# 05-Front_Panel_SFP_1.net
KiCad netlist of a schematic drawn in Altium Designer
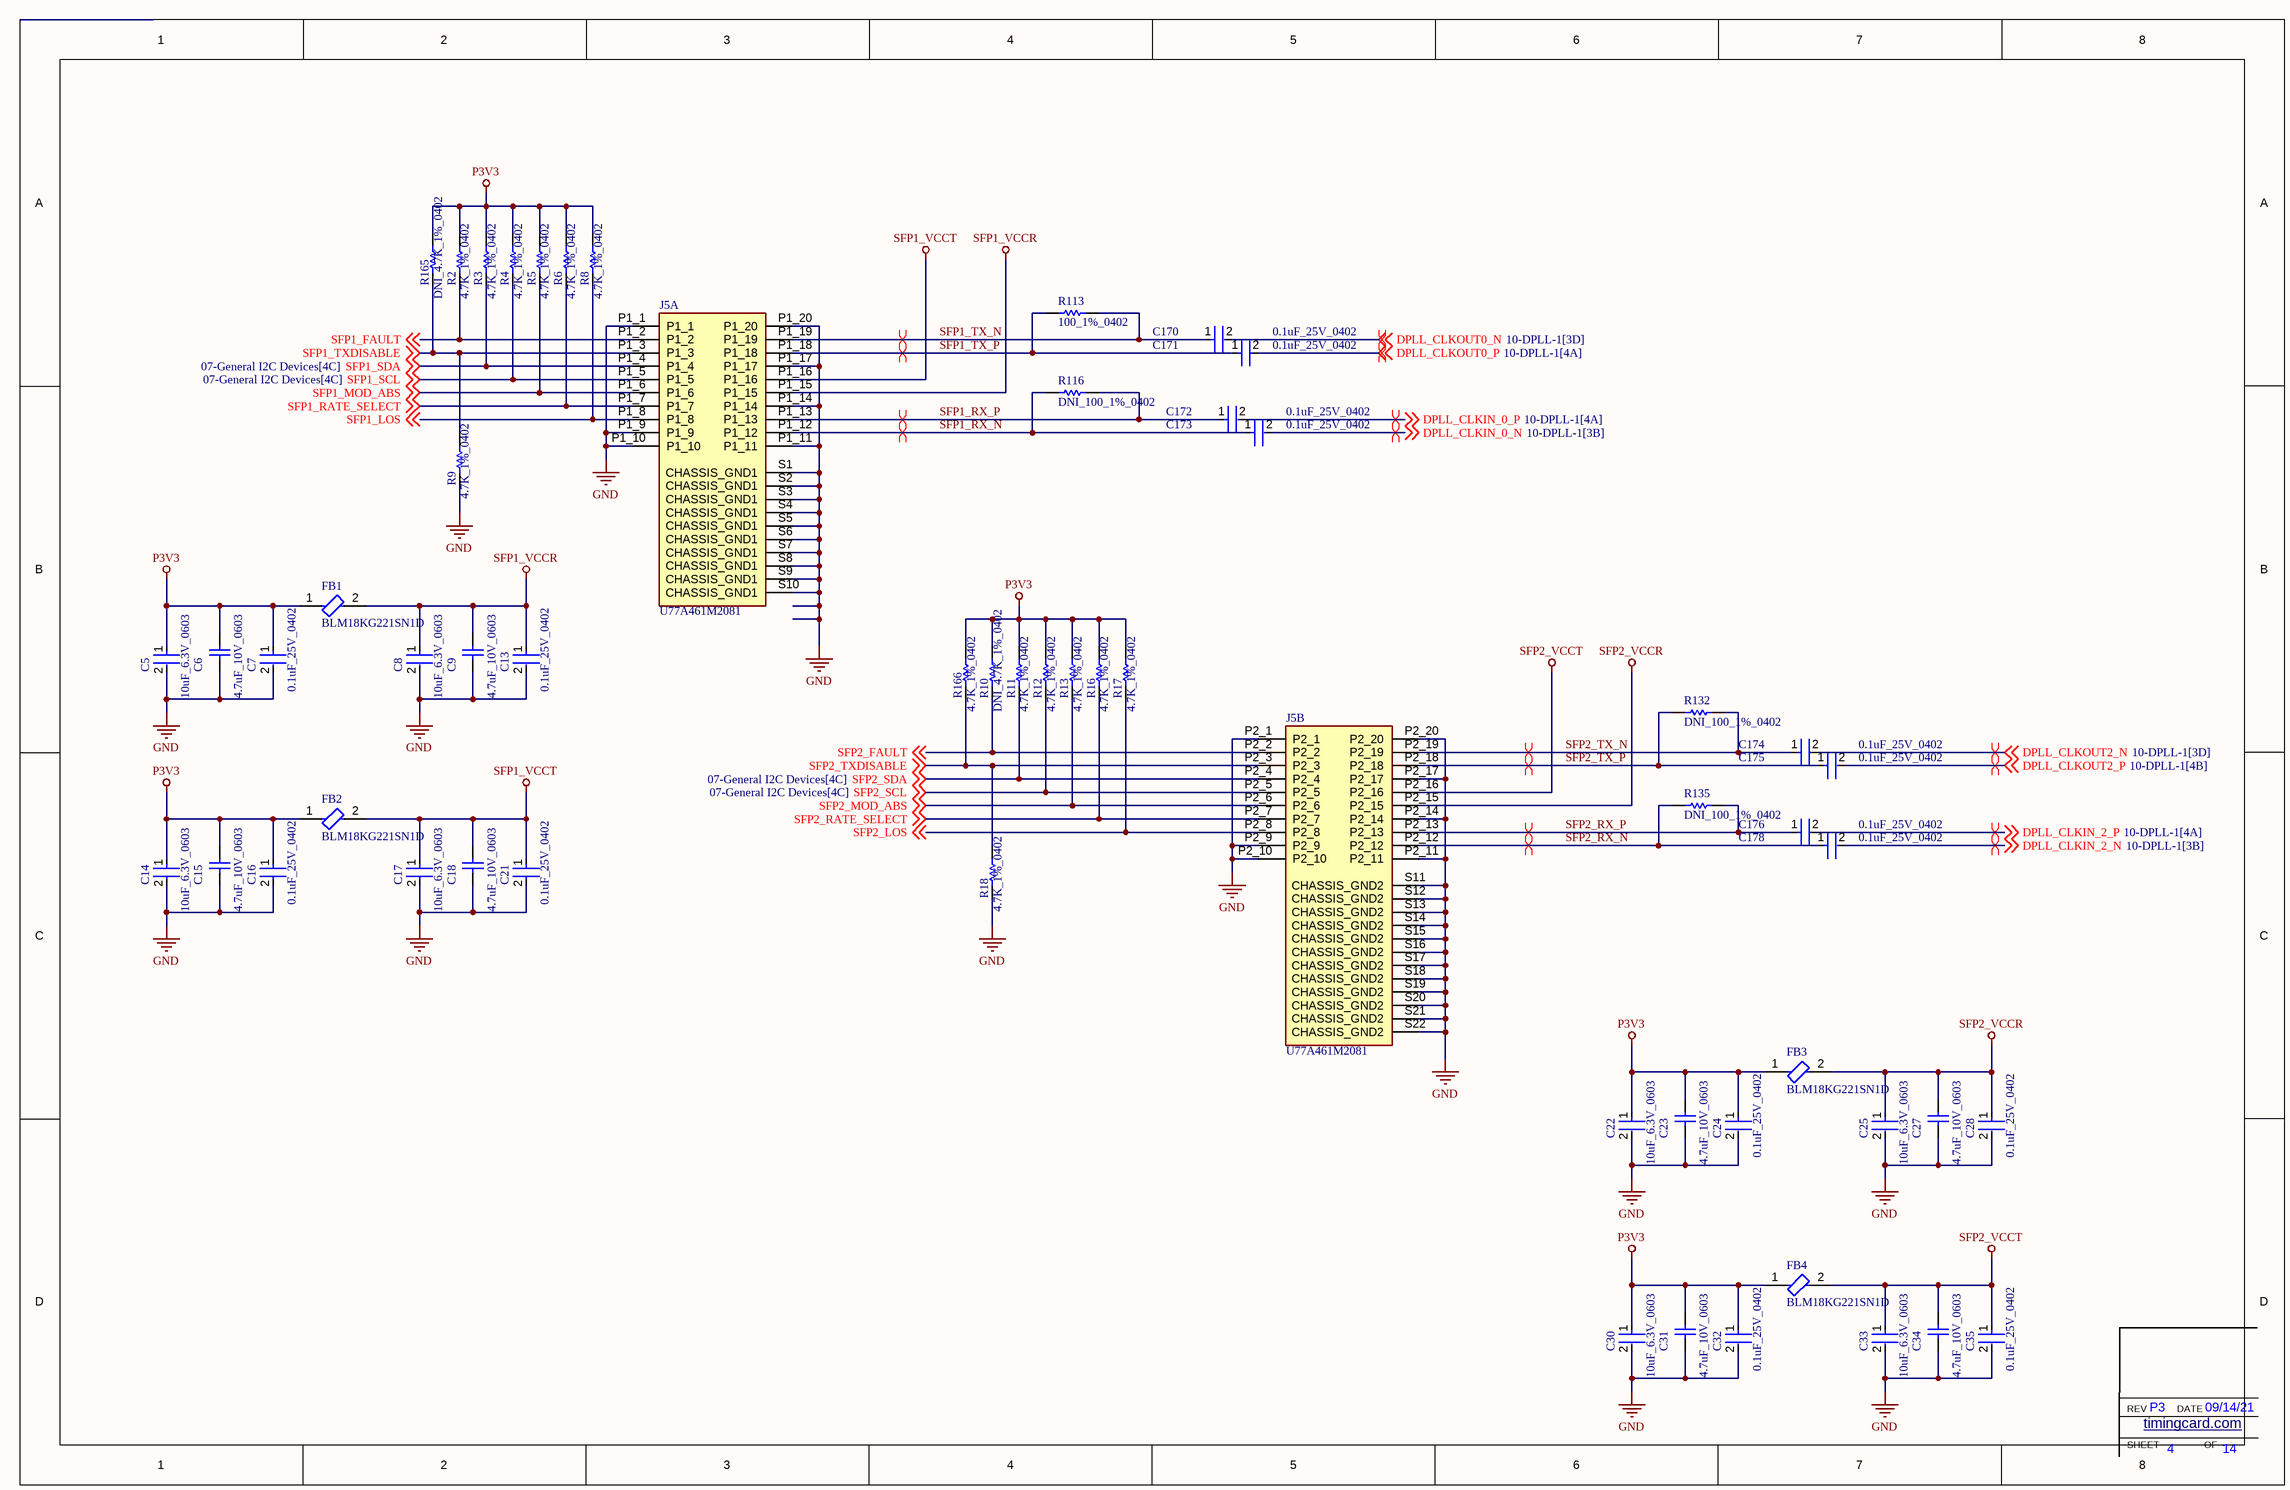
[diagram p0: 05-Front Panel SFP_1.SchDoc]

(export (version "E")
  (design (tool "Eeschema 10.0.6"))
  (components
    (comp (ref "C5")
      (value "10uF_6.3V_0603")
      (footprint "FP-C0603C106M9PACTU-MFG")
      (description "CAP CER 10UF 6.3V X5R 0603")
      (fields
        (field (name "MANUFACTURER PART NUMBER") "C0603C106M9PACTU")
        (field (name "MANUFACTURER") "Kemet")
      )
      (libsource (lib "Altium Content Vault") (part "b4654b650e69147ec39a6b967a45e02"))
    )
    (comp (ref "C6")
      (value "4.7uF_10V_0603")
      (footprint "CAPC1608X87X35NL15T15")
      (fields (field (name "PART NUMBER") "C0603C475K8PACTU") (field (name "MANUFACTURER") "Kemet"))
      (libsource (lib "Altium Content Vault") (part "CAP"))
    )
    (comp (ref "C7")
      (value "0.1uF_25V_0402")
      (footprint "FP-0402-L_1_0_1-W_0_5_0_1-IPC_C")
      (description "General Purpose Ceramic Capacitor, 0402, 100nF, 10%, X7R, 15%, 25V")
      (fields (field (name "VOLTAGE") "25V") (field (name "TOLERANCE") "10%"))
      (libsource (lib "Altium Content Vault") (part "b4654b650e69147ec39a6b967a45e02"))
    )
    (comp (ref "C8")
      (value "10uF_6.3V_0603")
      (footprint "FP-C0603C106M9PACTU-MFG")
      (description "CAP CER 10UF 6.3V X5R 0603")
      (fields
        (field (name "MANUFACTURER PART NUMBER") "C0603C106M9PACTU")
        (field (name "MANUFACTURER") "Kemet")
      )
      (libsource (lib "Altium Content Vault") (part "b4654b650e69147ec39a6b967a45e02"))
    )
    (comp (ref "C9")
      (value "4.7uF_10V_0603")
      (footprint "CAPC1608X87X35NL15T15")
      (fields (field (name "PART NUMBER") "C0603C475K8PACTU") (field (name "MANUFACTURER") "Kemet"))
      (libsource (lib "Altium Content Vault") (part "CAP"))
    )
    (comp (ref "C13")
      (value "0.1uF_25V_0402")
      (footprint "FP-0402-L_1_0_1-W_0_5_0_1-IPC_C")
      (description "General Purpose Ceramic Capacitor, 0402, 100nF, 10%, X7R, 15%, 25V")
      (fields (field (name "VOLTAGE") "25V") (field (name "TOLERANCE") "10%"))
      (libsource (lib "Altium Content Vault") (part "b4654b650e69147ec39a6b967a45e02"))
    )
    (comp (ref "C14")
      (value "10uF_6.3V_0603")
      (footprint "FP-C0603C106M9PACTU-MFG")
      (description "CAP CER 10UF 6.3V X5R 0603")
      (fields
        (field (name "MANUFACTURER PART NUMBER") "C0603C106M9PACTU")
        (field (name "MANUFACTURER") "Kemet")
      )
      (libsource (lib "Altium Content Vault") (part "b4654b650e69147ec39a6b967a45e02"))
    )
    (comp (ref "C15")
      (value "4.7uF_10V_0603")
      (footprint "CAPC1608X87X35NL15T15")
      (fields (field (name "PART NUMBER") "C0603C475K8PACTU") (field (name "MANUFACTURER") "Kemet"))
      (libsource (lib "Altium Content Vault") (part "CAP"))
    )
    (comp (ref "C16")
      (value "0.1uF_25V_0402")
      (footprint "FP-0402-L_1_0_1-W_0_5_0_1-IPC_C")
      (description "General Purpose Ceramic Capacitor, 0402, 100nF, 10%, X7R, 15%, 25V")
      (fields (field (name "VOLTAGE") "25V") (field (name "TOLERANCE") "10%"))
      (libsource (lib "Altium Content Vault") (part "b4654b650e69147ec39a6b967a45e02"))
    )
    (comp (ref "C17")
      (value "10uF_6.3V_0603")
      (footprint "FP-C0603C106M9PACTU-MFG")
      (description "CAP CER 10UF 6.3V X5R 0603")
      (fields
        (field (name "MANUFACTURER PART NUMBER") "C0603C106M9PACTU")
        (field (name "MANUFACTURER") "Kemet")
      )
      (libsource (lib "Altium Content Vault") (part "b4654b650e69147ec39a6b967a45e02"))
    )
    (comp (ref "C18")
      (value "4.7uF_10V_0603")
      (footprint "CAPC1608X87X35NL15T15")
      (fields (field (name "PART NUMBER") "C0603C475K8PACTU") (field (name "MANUFACTURER") "Kemet"))
      (libsource (lib "Altium Content Vault") (part "CAP"))
    )
    (comp (ref "C21")
      (value "0.1uF_25V_0402")
      (footprint "FP-0402-L_1_0_1-W_0_5_0_1-IPC_C")
      (description "General Purpose Ceramic Capacitor, 0402, 100nF, 10%, X7R, 15%, 25V")
      (fields (field (name "VOLTAGE") "25V") (field (name "TOLERANCE") "10%"))
      (libsource (lib "Altium Content Vault") (part "b4654b650e69147ec39a6b967a45e02"))
    )
    (comp (ref "C22")
      (value "10uF_6.3V_0603")
      (footprint "FP-C0603C106M9PACTU-MFG")
      (description "CAP CER 10UF 6.3V X5R 0603")
      (fields
        (field (name "MANUFACTURER PART NUMBER") "C0603C106M9PACTU")
        (field (name "MANUFACTURER") "Kemet")
      )
      (libsource (lib "Altium Content Vault") (part "b4654b650e69147ec39a6b967a45e02"))
    )
    (comp (ref "C23")
      (value "4.7uF_10V_0603")
      (footprint "CAPC1608X87X35NL15T15")
      (fields (field (name "PART NUMBER") "C0603C475K8PACTU") (field (name "MANUFACTURER") "Kemet"))
      (libsource (lib "Altium Content Vault") (part "CAP"))
    )
    (comp (ref "C24")
      (value "0.1uF_25V_0402")
      (footprint "FP-0402-L_1_0_1-W_0_5_0_1-IPC_C")
      (description "General Purpose Ceramic Capacitor, 0402, 100nF, 10%, X7R, 15%, 25V")
      (fields (field (name "VOLTAGE") "25V") (field (name "TOLERANCE") "10%"))
      (libsource (lib "Altium Content Vault") (part "b4654b650e69147ec39a6b967a45e02"))
    )
    (comp (ref "C25")
      (value "10uF_6.3V_0603")
      (footprint "FP-C0603C106M9PACTU-MFG")
      (description "CAP CER 10UF 6.3V X5R 0603")
      (fields
        (field (name "MANUFACTURER PART NUMBER") "C0603C106M9PACTU")
        (field (name "MANUFACTURER") "Kemet")
      )
      (libsource (lib "Altium Content Vault") (part "b4654b650e69147ec39a6b967a45e02"))
    )
    (comp (ref "C27")
      (value "4.7uF_10V_0603")
      (footprint "CAPC1608X87X35NL15T15")
      (fields (field (name "PART NUMBER") "C0603C475K8PACTU") (field (name "MANUFACTURER") "Kemet"))
      (libsource (lib "Altium Content Vault") (part "CAP"))
    )
    (comp (ref "C28")
      (value "0.1uF_25V_0402")
      (footprint "FP-0402-L_1_0_1-W_0_5_0_1-IPC_C")
      (description "General Purpose Ceramic Capacitor, 0402, 100nF, 10%, X7R, 15%, 25V")
      (fields (field (name "VOLTAGE") "25V") (field (name "TOLERANCE") "10%"))
      (libsource (lib "Altium Content Vault") (part "b4654b650e69147ec39a6b967a45e02"))
    )
    (comp (ref "C30")
      (value "10uF_6.3V_0603")
      (footprint "FP-C0603C106M9PACTU-MFG")
      (description "CAP CER 10UF 6.3V X5R 0603")
      (fields
        (field (name "MANUFACTURER PART NUMBER") "C0603C106M9PACTU")
        (field (name "MANUFACTURER") "Kemet")
      )
      (libsource (lib "Altium Content Vault") (part "b4654b650e69147ec39a6b967a45e02"))
    )
    (comp (ref "C31")
      (value "4.7uF_10V_0603")
      (footprint "CAPC1608X87X35NL15T15")
      (fields (field (name "PART NUMBER") "C0603C475K8PACTU") (field (name "MANUFACTURER") "Kemet"))
      (libsource (lib "Altium Content Vault") (part "CAP"))
    )
    (comp (ref "C32")
      (value "0.1uF_25V_0402")
      (footprint "FP-0402-L_1_0_1-W_0_5_0_1-IPC_C")
      (description "General Purpose Ceramic Capacitor, 0402, 100nF, 10%, X7R, 15%, 25V")
      (fields (field (name "VOLTAGE") "25V") (field (name "TOLERANCE") "10%"))
      (libsource (lib "Altium Content Vault") (part "b4654b650e69147ec39a6b967a45e02"))
    )
    (comp (ref "C33")
      (value "10uF_6.3V_0603")
      (footprint "FP-C0603C106M9PACTU-MFG")
      (description "CAP CER 10UF 6.3V X5R 0603")
      (fields
        (field (name "MANUFACTURER PART NUMBER") "C0603C106M9PACTU")
        (field (name "MANUFACTURER") "Kemet")
      )
      (libsource (lib "Altium Content Vault") (part "b4654b650e69147ec39a6b967a45e02"))
    )
    (comp (ref "C34")
      (value "4.7uF_10V_0603")
      (footprint "CAPC1608X87X35NL15T15")
      (fields (field (name "PART NUMBER") "C0603C475K8PACTU") (field (name "MANUFACTURER") "Kemet"))
      (libsource (lib "Altium Content Vault") (part "CAP"))
    )
    (comp (ref "C35")
      (value "0.1uF_25V_0402")
      (footprint "FP-0402-L_1_0_1-W_0_5_0_1-IPC_C")
      (description "General Purpose Ceramic Capacitor, 0402, 100nF, 10%, X7R, 15%, 25V")
      (fields (field (name "VOLTAGE") "25V") (field (name "TOLERANCE") "10%"))
      (libsource (lib "Altium Content Vault") (part "b4654b650e69147ec39a6b967a45e02"))
    )
    (comp (ref "C170")
      (value "0.1uF_25V_0402")
      (footprint "FP-0402-L_1_0_1-W_0_5_0_1-IPC_C")
      (description "General Purpose Ceramic Capacitor, 0402, 100nF, 10%, X7R, 15%, 25V")
      (fields (field (name "VOLTAGE") "25V") (field (name "TOLERANCE") "10%"))
      (libsource (lib "Altium Content Vault") (part "b4654b650e69147ec39a6b967a45e02"))
    )
    (comp (ref "C171")
      (value "0.1uF_25V_0402")
      (footprint "FP-0402-L_1_0_1-W_0_5_0_1-IPC_C")
      (description "General Purpose Ceramic Capacitor, 0402, 100nF, 10%, X7R, 15%, 25V")
      (fields (field (name "VOLTAGE") "25V") (field (name "TOLERANCE") "10%"))
      (libsource (lib "Altium Content Vault") (part "b4654b650e69147ec39a6b967a45e02"))
    )
    (comp (ref "C172")
      (value "0.1uF_25V_0402")
      (footprint "FP-0402-L_1_0_1-W_0_5_0_1-IPC_C")
      (description "General Purpose Ceramic Capacitor, 0402, 100nF, 10%, X7R, 15%, 25V")
      (fields (field (name "VOLTAGE") "25V") (field (name "TOLERANCE") "10%"))
      (libsource (lib "Altium Content Vault") (part "b4654b650e69147ec39a6b967a45e02"))
    )
    (comp (ref "C173")
      (value "0.1uF_25V_0402")
      (footprint "FP-0402-L_1_0_1-W_0_5_0_1-IPC_C")
      (description "General Purpose Ceramic Capacitor, 0402, 100nF, 10%, X7R, 15%, 25V")
      (fields (field (name "VOLTAGE") "25V") (field (name "TOLERANCE") "10%"))
      (libsource (lib "Altium Content Vault") (part "b4654b650e69147ec39a6b967a45e02"))
    )
    (comp (ref "C174")
      (value "0.1uF_25V_0402")
      (footprint "FP-0402-L_1_0_1-W_0_5_0_1-IPC_C")
      (description "General Purpose Ceramic Capacitor, 0402, 100nF, 10%, X7R, 15%, 25V")
      (fields (field (name "VOLTAGE") "25V") (field (name "TOLERANCE") "10%"))
      (libsource (lib "Altium Content Vault") (part "b4654b650e69147ec39a6b967a45e02"))
    )
    (comp (ref "C175")
      (value "0.1uF_25V_0402")
      (footprint "FP-0402-L_1_0_1-W_0_5_0_1-IPC_C")
      (description "General Purpose Ceramic Capacitor, 0402, 100nF, 10%, X7R, 15%, 25V")
      (fields (field (name "VOLTAGE") "25V") (field (name "TOLERANCE") "10%"))
      (libsource (lib "Altium Content Vault") (part "b4654b650e69147ec39a6b967a45e02"))
    )
    (comp (ref "C176")
      (value "0.1uF_25V_0402")
      (footprint "FP-0402-L_1_0_1-W_0_5_0_1-IPC_C")
      (description "General Purpose Ceramic Capacitor, 0402, 100nF, 10%, X7R, 15%, 25V")
      (fields (field (name "VOLTAGE") "25V") (field (name "TOLERANCE") "10%"))
      (libsource (lib "Altium Content Vault") (part "b4654b650e69147ec39a6b967a45e02"))
    )
    (comp (ref "C178")
      (value "0.1uF_25V_0402")
      (footprint "FP-0402-L_1_0_1-W_0_5_0_1-IPC_C")
      (description "General Purpose Ceramic Capacitor, 0402, 100nF, 10%, X7R, 15%, 25V")
      (fields (field (name "VOLTAGE") "25V") (field (name "TOLERANCE") "10%"))
      (libsource (lib "Altium Content Vault") (part "b4654b650e69147ec39a6b967a45e02"))
    )
    (comp (ref "FB1")
      (value "BLM18KG221SN1D")
      (footprint "FP-BLM18-0_15-t0_8-IPC_B")
      (description "Chip Ferrite Bead, 0603, 220Ω @ 100MHz, 0.05Ω, 25%, 2.2A")
      (fields (field (name "TOLERANCE") "25%"))
      (libsource (lib "Altium Content Vault") (part "5f30dd21d616792df468990f7003faa"))
    )
    (comp (ref "FB2")
      (value "BLM18KG221SN1D")
      (footprint "FP-BLM18-0_15-t0_8-IPC_B")
      (description "Chip Ferrite Bead, 0603, 220Ω @ 100MHz, 0.05Ω, 25%, 2.2A")
      (fields (field (name "TOLERANCE") "25%"))
      (libsource (lib "Altium Content Vault") (part "5f30dd21d616792df468990f7003faa"))
    )
    (comp (ref "FB3")
      (value "BLM18KG221SN1D")
      (footprint "FP-BLM18-0_15-t0_8-IPC_B")
      (description "Chip Ferrite Bead, 0603, 220Ω @ 100MHz, 0.05Ω, 25%, 2.2A")
      (fields (field (name "TOLERANCE") "25%"))
      (libsource (lib "Altium Content Vault") (part "5f30dd21d616792df468990f7003faa"))
    )
    (comp (ref "FB4")
      (value "BLM18KG221SN1D")
      (footprint "FP-BLM18-0_15-t0_8-IPC_B")
      (description "Chip Ferrite Bead, 0603, 220Ω @ 100MHz, 0.05Ω, 25%, 2.2A")
      (fields (field (name "TOLERANCE") "25%"))
      (libsource (lib "Altium Content Vault") (part "5f30dd21d616792df468990f7003faa"))
    )
    (comp (ref "J5")
      (value "U77A461M2081")
      (footprint "AMPHENOL_U77A461M2081")
      (fields (field (name "MF") "AMPHENOL ICC / FCI"))
      (libsource (lib "U77A461M2081") (part "U77A461M2081"))
    )
    (comp (ref "R2")
      (value "4.7K_1%_0402")
      (footprint "RESC1005X40X25NL10T10")
      (fields (field (name "MANUFACTURER") "Bourns") (field (name "PART NUMBER") "CR0402-FX-4701GLF"))
      (libsource (lib "Altium Content Vault") (part "RES"))
    )
    (comp (ref "R3")
      (value "4.7K_1%_0402")
      (footprint "RESC1005X40X25NL10T10")
      (fields (field (name "MANUFACTURER") "Bourns") (field (name "PART NUMBER") "CR0402-FX-4701GLF"))
      (libsource (lib "Altium Content Vault") (part "RES"))
    )
    (comp (ref "R4")
      (value "4.7K_1%_0402")
      (footprint "RESC1005X40X25NL10T10")
      (fields (field (name "MANUFACTURER") "Bourns") (field (name "PART NUMBER") "CR0402-FX-4701GLF"))
      (libsource (lib "Altium Content Vault") (part "RES"))
    )
    (comp (ref "R5")
      (value "4.7K_1%_0402")
      (footprint "RESC1005X40X25NL10T10")
      (fields (field (name "MANUFACTURER") "Bourns") (field (name "PART NUMBER") "CR0402-FX-4701GLF"))
      (libsource (lib "Altium Content Vault") (part "RES"))
    )
    (comp (ref "R6")
      (value "4.7K_1%_0402")
      (footprint "RESC1005X40X25NL10T10")
      (fields (field (name "MANUFACTURER") "Bourns") (field (name "PART NUMBER") "CR0402-FX-4701GLF"))
      (libsource (lib "Altium Content Vault") (part "RES"))
    )
    (comp (ref "R8")
      (value "4.7K_1%_0402")
      (footprint "RESC1005X40X25NL10T10")
      (fields (field (name "MANUFACTURER") "Bourns") (field (name "PART NUMBER") "CR0402-FX-4701GLF"))
      (libsource (lib "Altium Content Vault") (part "RES"))
    )
    (comp (ref "R9")
      (value "4.7K_1%_0402")
      (footprint "RESC1005X40X25NL10T10")
      (fields (field (name "MANUFACTURER") "Bourns") (field (name "PART NUMBER") "CR0402-FX-4701GLF"))
      (libsource (lib "Altium Content Vault") (part "RES"))
    )
    (comp (ref "R10")
      (value "DNI_4.7K_1%_0402")
      (footprint "RESC1005X40X25NL10T10")
      (fields (field (name "MANUFACTURER") "Bourns") (field (name "PART NUMBER") "CR0402-FX-4701GLF"))
      (libsource (lib "Altium Content Vault") (part "RES"))
    )
    (comp (ref "R11")
      (value "4.7K_1%_0402")
      (footprint "RESC1005X40X25NL10T10")
      (fields (field (name "MANUFACTURER") "Bourns") (field (name "PART NUMBER") "CR0402-FX-4701GLF"))
      (libsource (lib "Altium Content Vault") (part "RES"))
    )
    (comp (ref "R12")
      (value "4.7K_1%_0402")
      (footprint "RESC1005X40X25NL10T10")
      (fields (field (name "MANUFACTURER") "Bourns") (field (name "PART NUMBER") "CR0402-FX-4701GLF"))
      (libsource (lib "Altium Content Vault") (part "RES"))
    )
    (comp (ref "R13")
      (value "4.7K_1%_0402")
      (footprint "RESC1005X40X25NL10T10")
      (fields (field (name "MANUFACTURER") "Bourns") (field (name "PART NUMBER") "CR0402-FX-4701GLF"))
      (libsource (lib "Altium Content Vault") (part "RES"))
    )
    (comp (ref "R16")
      (value "4.7K_1%_0402")
      (footprint "RESC1005X40X25NL10T10")
      (fields (field (name "MANUFACTURER") "Bourns") (field (name "PART NUMBER") "CR0402-FX-4701GLF"))
      (libsource (lib "Altium Content Vault") (part "RES"))
    )
    (comp (ref "R17")
      (value "4.7K_1%_0402")
      (footprint "RESC1005X40X25NL10T10")
      (fields (field (name "MANUFACTURER") "Bourns") (field (name "PART NUMBER") "CR0402-FX-4701GLF"))
      (libsource (lib "Altium Content Vault") (part "RES"))
    )
    (comp (ref "R18")
      (value "4.7K_1%_0402")
      (footprint "RESC1005X40X25NL10T10")
      (fields (field (name "MANUFACTURER") "Bourns") (field (name "PART NUMBER") "CR0402-FX-4701GLF"))
      (libsource (lib "Altium Content Vault") (part "RES"))
    )
    (comp (ref "R113")
      (value "100_1%_0402")
      (footprint "RESC1005X40X25NL05T10")
      (fields (field (name "MANUFACTURER") "Yageo") (field (name "PART NUMBER") "RC0402FR-13100RL"))
      (libsource (lib "Altium Content Vault") (part "RES"))
    )
    (comp (ref "R116")
      (value "DNI_100_1%_0402")
      (footprint "RESC1005X40X25NL05T10")
      (fields (field (name "MANUFACTURER") "Yageo") (field (name "PART NUMBER") "RC0402FR-13100RL"))
      (libsource (lib "Altium Content Vault") (part "RES"))
    )
    (comp (ref "R132")
      (value "DNI_100_1%_0402")
      (footprint "RESC1005X40X25NL05T10")
      (fields (field (name "MANUFACTURER") "Yageo") (field (name "PART NUMBER") "RC0402FR-13100RL"))
      (libsource (lib "Altium Content Vault") (part "RES"))
    )
    (comp (ref "R135")
      (value "DNI_100_1%_0402")
      (footprint "RESC1005X40X25NL05T10")
      (fields (field (name "MANUFACTURER") "Yageo") (field (name "PART NUMBER") "RC0402FR-13100RL"))
      (libsource (lib "Altium Content Vault") (part "RES"))
    )
    (comp (ref "R165")
      (value "DNI_4.7K_1%_0402")
      (footprint "RESC1005X40X25NL10T10")
      (fields (field (name "MANUFACTURER") "Bourns") (field (name "PART NUMBER") "CR0402-FX-4701GLF"))
      (libsource (lib "Altium Content Vault") (part "RES"))
    )
    (comp (ref "R166")
      (value "4.7K_1%_0402")
      (footprint "RESC1005X40X25NL10T10")
      (fields (field (name "MANUFACTURER") "Bourns") (field (name "PART NUMBER") "CR0402-FX-4701GLF"))
      (libsource (lib "Altium Content Vault") (part "RES"))
    )
  )
  (nets
    (net (code "1") (name "/SFP1_RX_N") (class "Default")
      (node (ref "C173") (pin "1") (pinfunction "1_1") (pintype "passive"))
      (node (ref "J5") (pin "P1_12") (pinfunction "P1_12_P1_12") (pintype "passive"))
      (node (ref "R116") (pin "1") (pinfunction "1_1") (pintype "passive"))
    )
    (net (code "2") (name "/SFP1_RX_P") (class "Default")
      (node (ref "C172") (pin "1") (pinfunction "1_1") (pintype "passive"))
      (node (ref "J5") (pin "P1_13") (pinfunction "P1_13_P1_13") (pintype "passive"))
      (node (ref "R116") (pin "2") (pinfunction "2_2") (pintype "passive"))
    )
    (net (code "3") (name "/SFP1_TX_N") (class "Default")
      (node (ref "C170") (pin "1") (pinfunction "1_1") (pintype "passive"))
      (node (ref "J5") (pin "P1_19") (pinfunction "P1_19_P1_19") (pintype "passive"))
      (node (ref "R113") (pin "2") (pinfunction "2_2") (pintype "passive"))
    )
    (net (code "4") (name "/SFP1_TX_P") (class "Default")
      (node (ref "C171") (pin "1") (pinfunction "1_1") (pintype "passive"))
      (node (ref "J5") (pin "P1_18") (pinfunction "P1_18_P1_18") (pintype "passive"))
      (node (ref "R113") (pin "1") (pinfunction "1_1") (pintype "passive"))
    )
    (net (code "5") (name "/SFP2_RX_N") (class "Default")
      (node (ref "C178") (pin "1") (pinfunction "1_1") (pintype "passive"))
      (node (ref "J5") (pin "P2_12") (pinfunction "P2_12_P2_12") (pintype "passive"))
      (node (ref "R135") (pin "1") (pinfunction "1_1") (pintype "passive"))
    )
    (net (code "6") (name "/SFP2_RX_P") (class "Default")
      (node (ref "C176") (pin "1") (pinfunction "1_1") (pintype "passive"))
      (node (ref "J5") (pin "P2_13") (pinfunction "P2_13_P2_13") (pintype "passive"))
      (node (ref "R135") (pin "2") (pinfunction "2_2") (pintype "passive"))
    )
    (net (code "7") (name "/SFP2_TX_N") (class "Default")
      (node (ref "C174") (pin "1") (pinfunction "1_1") (pintype "passive"))
      (node (ref "J5") (pin "P2_19") (pinfunction "P2_19_P2_19") (pintype "passive"))
      (node (ref "R132") (pin "2") (pinfunction "2_2") (pintype "passive"))
    )
    (net (code "8") (name "/SFP2_TX_P") (class "Default")
      (node (ref "C175") (pin "1") (pinfunction "1_1") (pintype "passive"))
      (node (ref "J5") (pin "P2_18") (pinfunction "P2_18_P2_18") (pintype "passive"))
      (node (ref "R132") (pin "1") (pinfunction "1_1") (pintype "passive"))
    )
    (net (code "9") (name "DPLL_CLKIN_0_N") (class "Default")
      (node (ref "C173") (pin "2") (pinfunction "2_2") (pintype "passive"))
    )
    (net (code "10") (name "DPLL_CLKIN_0_P") (class "Default")
      (node (ref "C172") (pin "2") (pinfunction "2_2") (pintype "passive"))
    )
    (net (code "11") (name "DPLL_CLKIN_2_N") (class "Default")
      (node (ref "C178") (pin "2") (pinfunction "2_2") (pintype "passive"))
    )
    (net (code "12") (name "DPLL_CLKIN_2_P") (class "Default")
      (node (ref "C176") (pin "2") (pinfunction "2_2") (pintype "passive"))
    )
    (net (code "13") (name "DPLL_CLKOUT0_N") (class "Default")
      (node (ref "C170") (pin "2") (pinfunction "2_2") (pintype "passive"))
    )
    (net (code "14") (name "DPLL_CLKOUT0_P") (class "Default")
      (node (ref "C171") (pin "2") (pinfunction "2_2") (pintype "passive"))
    )
    (net (code "15") (name "DPLL_CLKOUT2_N") (class "Default")
      (node (ref "C174") (pin "2") (pinfunction "2_2") (pintype "passive"))
    )
    (net (code "16") (name "DPLL_CLKOUT2_P") (class "Default")
      (node (ref "C175") (pin "2") (pinfunction "2_2") (pintype "passive"))
    )
    (net (code "17") (name "GND") (class "Default")
      (node (ref "C13") (pin "2") (pinfunction "2_2") (pintype "passive"))
      (node (ref "C14") (pin "2") (pinfunction "2_2") (pintype "passive"))
      (node (ref "C15") (pin "1") (pinfunction "1_1") (pintype "passive"))
      (node (ref "C16") (pin "2") (pinfunction "2_2") (pintype "passive"))
      (node (ref "C17") (pin "2") (pinfunction "2_2") (pintype "passive"))
      (node (ref "C18") (pin "1") (pinfunction "1_1") (pintype "passive"))
      (node (ref "C21") (pin "2") (pinfunction "2_2") (pintype "passive"))
      (node (ref "C22") (pin "2") (pinfunction "2_2") (pintype "passive"))
      (node (ref "C23") (pin "1") (pinfunction "1_1") (pintype "passive"))
      (node (ref "C24") (pin "2") (pinfunction "2_2") (pintype "passive"))
      (node (ref "C25") (pin "2") (pinfunction "2_2") (pintype "passive"))
      (node (ref "C27") (pin "1") (pinfunction "1_1") (pintype "passive"))
      (node (ref "C28") (pin "2") (pinfunction "2_2") (pintype "passive"))
      (node (ref "C30") (pin "2") (pinfunction "2_2") (pintype "passive"))
      (node (ref "C31") (pin "1") (pinfunction "1_1") (pintype "passive"))
      (node (ref "C32") (pin "2") (pinfunction "2_2") (pintype "passive"))
      (node (ref "C33") (pin "2") (pinfunction "2_2") (pintype "passive"))
      (node (ref "C34") (pin "1") (pinfunction "1_1") (pintype "passive"))
      (node (ref "C35") (pin "2") (pinfunction "2_2") (pintype "passive"))
      (node (ref "C5") (pin "2") (pinfunction "2_2") (pintype "passive"))
      (node (ref "C6") (pin "1") (pinfunction "1_1") (pintype "passive"))
      (node (ref "C7") (pin "2") (pinfunction "2_2") (pintype "passive"))
      (node (ref "C8") (pin "2") (pinfunction "2_2") (pintype "passive"))
      (node (ref "C9") (pin "1") (pinfunction "1_1") (pintype "passive"))
      (node (ref "J5") (pin "P1_1") (pinfunction "P1_1_P1_1") (pintype "passive"))
      (node (ref "J5") (pin "P1_10") (pinfunction "P1_10_P1_10") (pintype "passive"))
      (node (ref "J5") (pin "P1_11") (pinfunction "P1_11_P1_11") (pintype "passive"))
      (node (ref "J5") (pin "P1_14") (pinfunction "P1_14_P1_14") (pintype "passive"))
      (node (ref "J5") (pin "P1_17") (pinfunction "P1_17_P1_17") (pintype "passive"))
      (node (ref "J5") (pin "P1_20") (pinfunction "P1_20_P1_20") (pintype "passive"))
      (node (ref "J5") (pin "P1_9") (pinfunction "P1_9_P1_9") (pintype "passive"))
      (node (ref "J5") (pin "P2_1") (pinfunction "P2_1_P2_1") (pintype "passive"))
      (node (ref "J5") (pin "P2_10") (pinfunction "P2_10_P2_10") (pintype "passive"))
      (node (ref "J5") (pin "P2_11") (pinfunction "P2_11_P2_11") (pintype "passive"))
      (node (ref "J5") (pin "P2_14") (pinfunction "P2_14_P2_14") (pintype "passive"))
      (node (ref "J5") (pin "P2_17") (pinfunction "P2_17_P2_17") (pintype "passive"))
      (node (ref "J5") (pin "P2_20") (pinfunction "P2_20_P2_20") (pintype "passive"))
      (node (ref "J5") (pin "P2_9") (pinfunction "P2_9_P2_9") (pintype "passive"))
      (node (ref "J5") (pin "S1") (pinfunction "CHASSIS_GND1_S1") (pintype "power_in"))
      (node (ref "J5") (pin "S10") (pinfunction "CHASSIS_GND1_S10") (pintype "power_in"))
      (node (ref "J5") (pin "S11") (pinfunction "CHASSIS_GND2_S11") (pintype "passive"))
      (node (ref "J5") (pin "S12") (pinfunction "CHASSIS_GND2_S12") (pintype "passive"))
      (node (ref "J5") (pin "S13") (pinfunction "CHASSIS_GND2_S13") (pintype "passive"))
      (node (ref "J5") (pin "S14") (pinfunction "CHASSIS_GND2_S14") (pintype "passive"))
      (node (ref "J5") (pin "S15") (pinfunction "CHASSIS_GND2_S15") (pintype "passive"))
      (node (ref "J5") (pin "S16") (pinfunction "CHASSIS_GND2_S16") (pintype "passive"))
      (node (ref "J5") (pin "S17") (pinfunction "CHASSIS_GND2_S17") (pintype "passive"))
      (node (ref "J5") (pin "S18") (pinfunction "CHASSIS_GND2_S18") (pintype "passive"))
      (node (ref "J5") (pin "S19") (pinfunction "CHASSIS_GND2_S19") (pintype "passive"))
      (node (ref "J5") (pin "S2") (pinfunction "CHASSIS_GND1_S2") (pintype "power_in"))
      (node (ref "J5") (pin "S20") (pinfunction "CHASSIS_GND2_S20") (pintype "passive"))
      (node (ref "J5") (pin "S21") (pinfunction "CHASSIS_GND2_S21") (pintype "passive"))
      (node (ref "J5") (pin "S22") (pinfunction "CHASSIS_GND2_S22") (pintype "passive"))
      (node (ref "J5") (pin "S3") (pinfunction "CHASSIS_GND1_S3") (pintype "power_in"))
      (node (ref "J5") (pin "S4") (pinfunction "CHASSIS_GND1_S4") (pintype "power_in"))
      (node (ref "J5") (pin "S5") (pinfunction "CHASSIS_GND1_S5") (pintype "power_in"))
      (node (ref "J5") (pin "S6") (pinfunction "CHASSIS_GND1_S6") (pintype "power_in"))
      (node (ref "J5") (pin "S7") (pinfunction "CHASSIS_GND1_S7") (pintype "power_in"))
      (node (ref "J5") (pin "S8") (pinfunction "CHASSIS_GND1_S8") (pintype "power_in"))
      (node (ref "J5") (pin "S9") (pinfunction "CHASSIS_GND1_S9") (pintype "power_in"))
      (node (ref "R18") (pin "2") (pinfunction "2_2") (pintype "passive"))
      (node (ref "R9") (pin "2") (pinfunction "2_2") (pintype "passive"))
    )
    (net (code "18") (name "P3V3") (class "Default")
      (node (ref "C14") (pin "1") (pinfunction "1_1") (pintype "passive"))
      (node (ref "C15") (pin "2") (pinfunction "2_2") (pintype "passive"))
      (node (ref "C16") (pin "1") (pinfunction "1_1") (pintype "passive"))
      (node (ref "C22") (pin "1") (pinfunction "1_1") (pintype "passive"))
      (node (ref "C23") (pin "2") (pinfunction "2_2") (pintype "passive"))
      (node (ref "C24") (pin "1") (pinfunction "1_1") (pintype "passive"))
      (node (ref "C30") (pin "1") (pinfunction "1_1") (pintype "passive"))
      (node (ref "C31") (pin "2") (pinfunction "2_2") (pintype "passive"))
      (node (ref "C32") (pin "1") (pinfunction "1_1") (pintype "passive"))
      (node (ref "C5") (pin "1") (pinfunction "1_1") (pintype "passive"))
      (node (ref "C6") (pin "2") (pinfunction "2_2") (pintype "passive"))
      (node (ref "C7") (pin "1") (pinfunction "1_1") (pintype "passive"))
      (node (ref "FB1") (pin "1") (pinfunction "1_1") (pintype "passive"))
      (node (ref "FB2") (pin "1") (pinfunction "1_1") (pintype "passive"))
      (node (ref "FB3") (pin "1") (pinfunction "1_1") (pintype "passive"))
      (node (ref "FB4") (pin "1") (pinfunction "1_1") (pintype "passive"))
      (node (ref "R10") (pin "1") (pinfunction "1_1") (pintype "passive"))
      (node (ref "R11") (pin "1") (pinfunction "1_1") (pintype "passive"))
      (node (ref "R12") (pin "1") (pinfunction "1_1") (pintype "passive"))
      (node (ref "R13") (pin "1") (pinfunction "1_1") (pintype "passive"))
      (node (ref "R16") (pin "1") (pinfunction "1_1") (pintype "passive"))
      (node (ref "R165") (pin "1") (pinfunction "1_1") (pintype "passive"))
      (node (ref "R166") (pin "1") (pinfunction "1_1") (pintype "passive"))
      (node (ref "R17") (pin "1") (pinfunction "1_1") (pintype "passive"))
      (node (ref "R2") (pin "1") (pinfunction "1_1") (pintype "passive"))
      (node (ref "R3") (pin "1") (pinfunction "1_1") (pintype "passive"))
      (node (ref "R4") (pin "1") (pinfunction "1_1") (pintype "passive"))
      (node (ref "R5") (pin "1") (pinfunction "1_1") (pintype "passive"))
      (node (ref "R6") (pin "1") (pinfunction "1_1") (pintype "passive"))
      (node (ref "R8") (pin "1") (pinfunction "1_1") (pintype "passive"))
    )
    (net (code "19") (name "SFP1_FAULT") (class "Default")
      (node (ref "J5") (pin "P1_2") (pinfunction "P1_2_P1_2") (pintype "passive"))
      (node (ref "R2") (pin "2") (pinfunction "2_2") (pintype "passive"))
    )
    (net (code "20") (name "SFP1_LOS") (class "Default")
      (node (ref "J5") (pin "P1_8") (pinfunction "P1_8_P1_8") (pintype "passive"))
      (node (ref "R8") (pin "2") (pinfunction "2_2") (pintype "passive"))
    )
    (net (code "21") (name "SFP1_MOD_ABS") (class "Default")
      (node (ref "J5") (pin "P1_6") (pinfunction "P1_6_P1_6") (pintype "passive"))
      (node (ref "R5") (pin "2") (pinfunction "2_2") (pintype "passive"))
    )
    (net (code "22") (name "SFP1_RATE_SELECT") (class "Default")
      (node (ref "J5") (pin "P1_7") (pinfunction "P1_7_P1_7") (pintype "passive"))
      (node (ref "R6") (pin "2") (pinfunction "2_2") (pintype "passive"))
    )
    (net (code "23") (name "SFP1_SCL") (class "Default")
      (node (ref "J5") (pin "P1_5") (pinfunction "P1_5_P1_5") (pintype "passive"))
      (node (ref "R4") (pin "2") (pinfunction "2_2") (pintype "passive"))
    )
    (net (code "24") (name "SFP1_SDA") (class "Default")
      (node (ref "J5") (pin "P1_4") (pinfunction "P1_4_P1_4") (pintype "passive"))
      (node (ref "R3") (pin "2") (pinfunction "2_2") (pintype "passive"))
    )
    (net (code "25") (name "SFP1_TXDISABLE") (class "Default")
      (node (ref "J5") (pin "P1_3") (pinfunction "P1_3_P1_3") (pintype "passive"))
      (node (ref "R165") (pin "2") (pinfunction "2_2") (pintype "passive"))
      (node (ref "R9") (pin "1") (pinfunction "1_1") (pintype "passive"))
    )
    (net (code "26") (name "SFP1_VCCR") (class "Default")
      (node (ref "C13") (pin "1") (pinfunction "1_1") (pintype "passive"))
      (node (ref "C8") (pin "1") (pinfunction "1_1") (pintype "passive"))
      (node (ref "C9") (pin "2") (pinfunction "2_2") (pintype "passive"))
      (node (ref "FB1") (pin "2") (pinfunction "2_2") (pintype "passive"))
      (node (ref "J5") (pin "P1_15") (pinfunction "P1_15_P1_15") (pintype "passive"))
    )
    (net (code "27") (name "SFP1_VCCT") (class "Default")
      (node (ref "C17") (pin "1") (pinfunction "1_1") (pintype "passive"))
      (node (ref "C18") (pin "2") (pinfunction "2_2") (pintype "passive"))
      (node (ref "C21") (pin "1") (pinfunction "1_1") (pintype "passive"))
      (node (ref "FB2") (pin "2") (pinfunction "2_2") (pintype "passive"))
      (node (ref "J5") (pin "P1_16") (pinfunction "P1_16_P1_16") (pintype "passive"))
    )
    (net (code "28") (name "SFP2_FAULT") (class "Default")
      (node (ref "J5") (pin "P2_2") (pinfunction "P2_2_P2_2") (pintype "passive"))
      (node (ref "R10") (pin "2") (pinfunction "2_2") (pintype "passive"))
    )
    (net (code "29") (name "SFP2_LOS") (class "Default")
      (node (ref "J5") (pin "P2_8") (pinfunction "P2_8_P2_8") (pintype "passive"))
      (node (ref "R17") (pin "2") (pinfunction "2_2") (pintype "passive"))
    )
    (net (code "30") (name "SFP2_MOD_ABS") (class "Default")
      (node (ref "J5") (pin "P2_6") (pinfunction "P2_6_P2_6") (pintype "passive"))
      (node (ref "R13") (pin "2") (pinfunction "2_2") (pintype "passive"))
    )
    (net (code "31") (name "SFP2_RATE_SELECT") (class "Default")
      (node (ref "J5") (pin "P2_7") (pinfunction "P2_7_P2_7") (pintype "passive"))
      (node (ref "R16") (pin "2") (pinfunction "2_2") (pintype "passive"))
    )
    (net (code "32") (name "SFP2_SCL") (class "Default")
      (node (ref "J5") (pin "P2_5") (pinfunction "P2_5_P2_5") (pintype "passive"))
      (node (ref "R12") (pin "2") (pinfunction "2_2") (pintype "passive"))
    )
    (net (code "33") (name "SFP2_SDA") (class "Default")
      (node (ref "J5") (pin "P2_4") (pinfunction "P2_4_P2_4") (pintype "passive"))
      (node (ref "R11") (pin "2") (pinfunction "2_2") (pintype "passive"))
    )
    (net (code "34") (name "SFP2_TXDISABLE") (class "Default")
      (node (ref "J5") (pin "P2_3") (pinfunction "P2_3_P2_3") (pintype "passive"))
      (node (ref "R166") (pin "2") (pinfunction "2_2") (pintype "passive"))
      (node (ref "R18") (pin "1") (pinfunction "1_1") (pintype "passive"))
    )
    (net (code "35") (name "SFP2_VCCR") (class "Default")
      (node (ref "C25") (pin "1") (pinfunction "1_1") (pintype "passive"))
      (node (ref "C27") (pin "2") (pinfunction "2_2") (pintype "passive"))
      (node (ref "C28") (pin "1") (pinfunction "1_1") (pintype "passive"))
      (node (ref "FB3") (pin "2") (pinfunction "2_2") (pintype "passive"))
      (node (ref "J5") (pin "P2_15") (pinfunction "P2_15_P2_15") (pintype "passive"))
    )
    (net (code "36") (name "SFP2_VCCT") (class "Default")
      (node (ref "C33") (pin "1") (pinfunction "1_1") (pintype "passive"))
      (node (ref "C34") (pin "2") (pinfunction "2_2") (pintype "passive"))
      (node (ref "C35") (pin "1") (pinfunction "1_1") (pintype "passive"))
      (node (ref "FB4") (pin "2") (pinfunction "2_2") (pintype "passive"))
      (node (ref "J5") (pin "P2_16") (pinfunction "P2_16_P2_16") (pintype "passive"))
    )
  )
)
